# MCU.net
KiCad netlist of a schematic drawn in Altium Designer
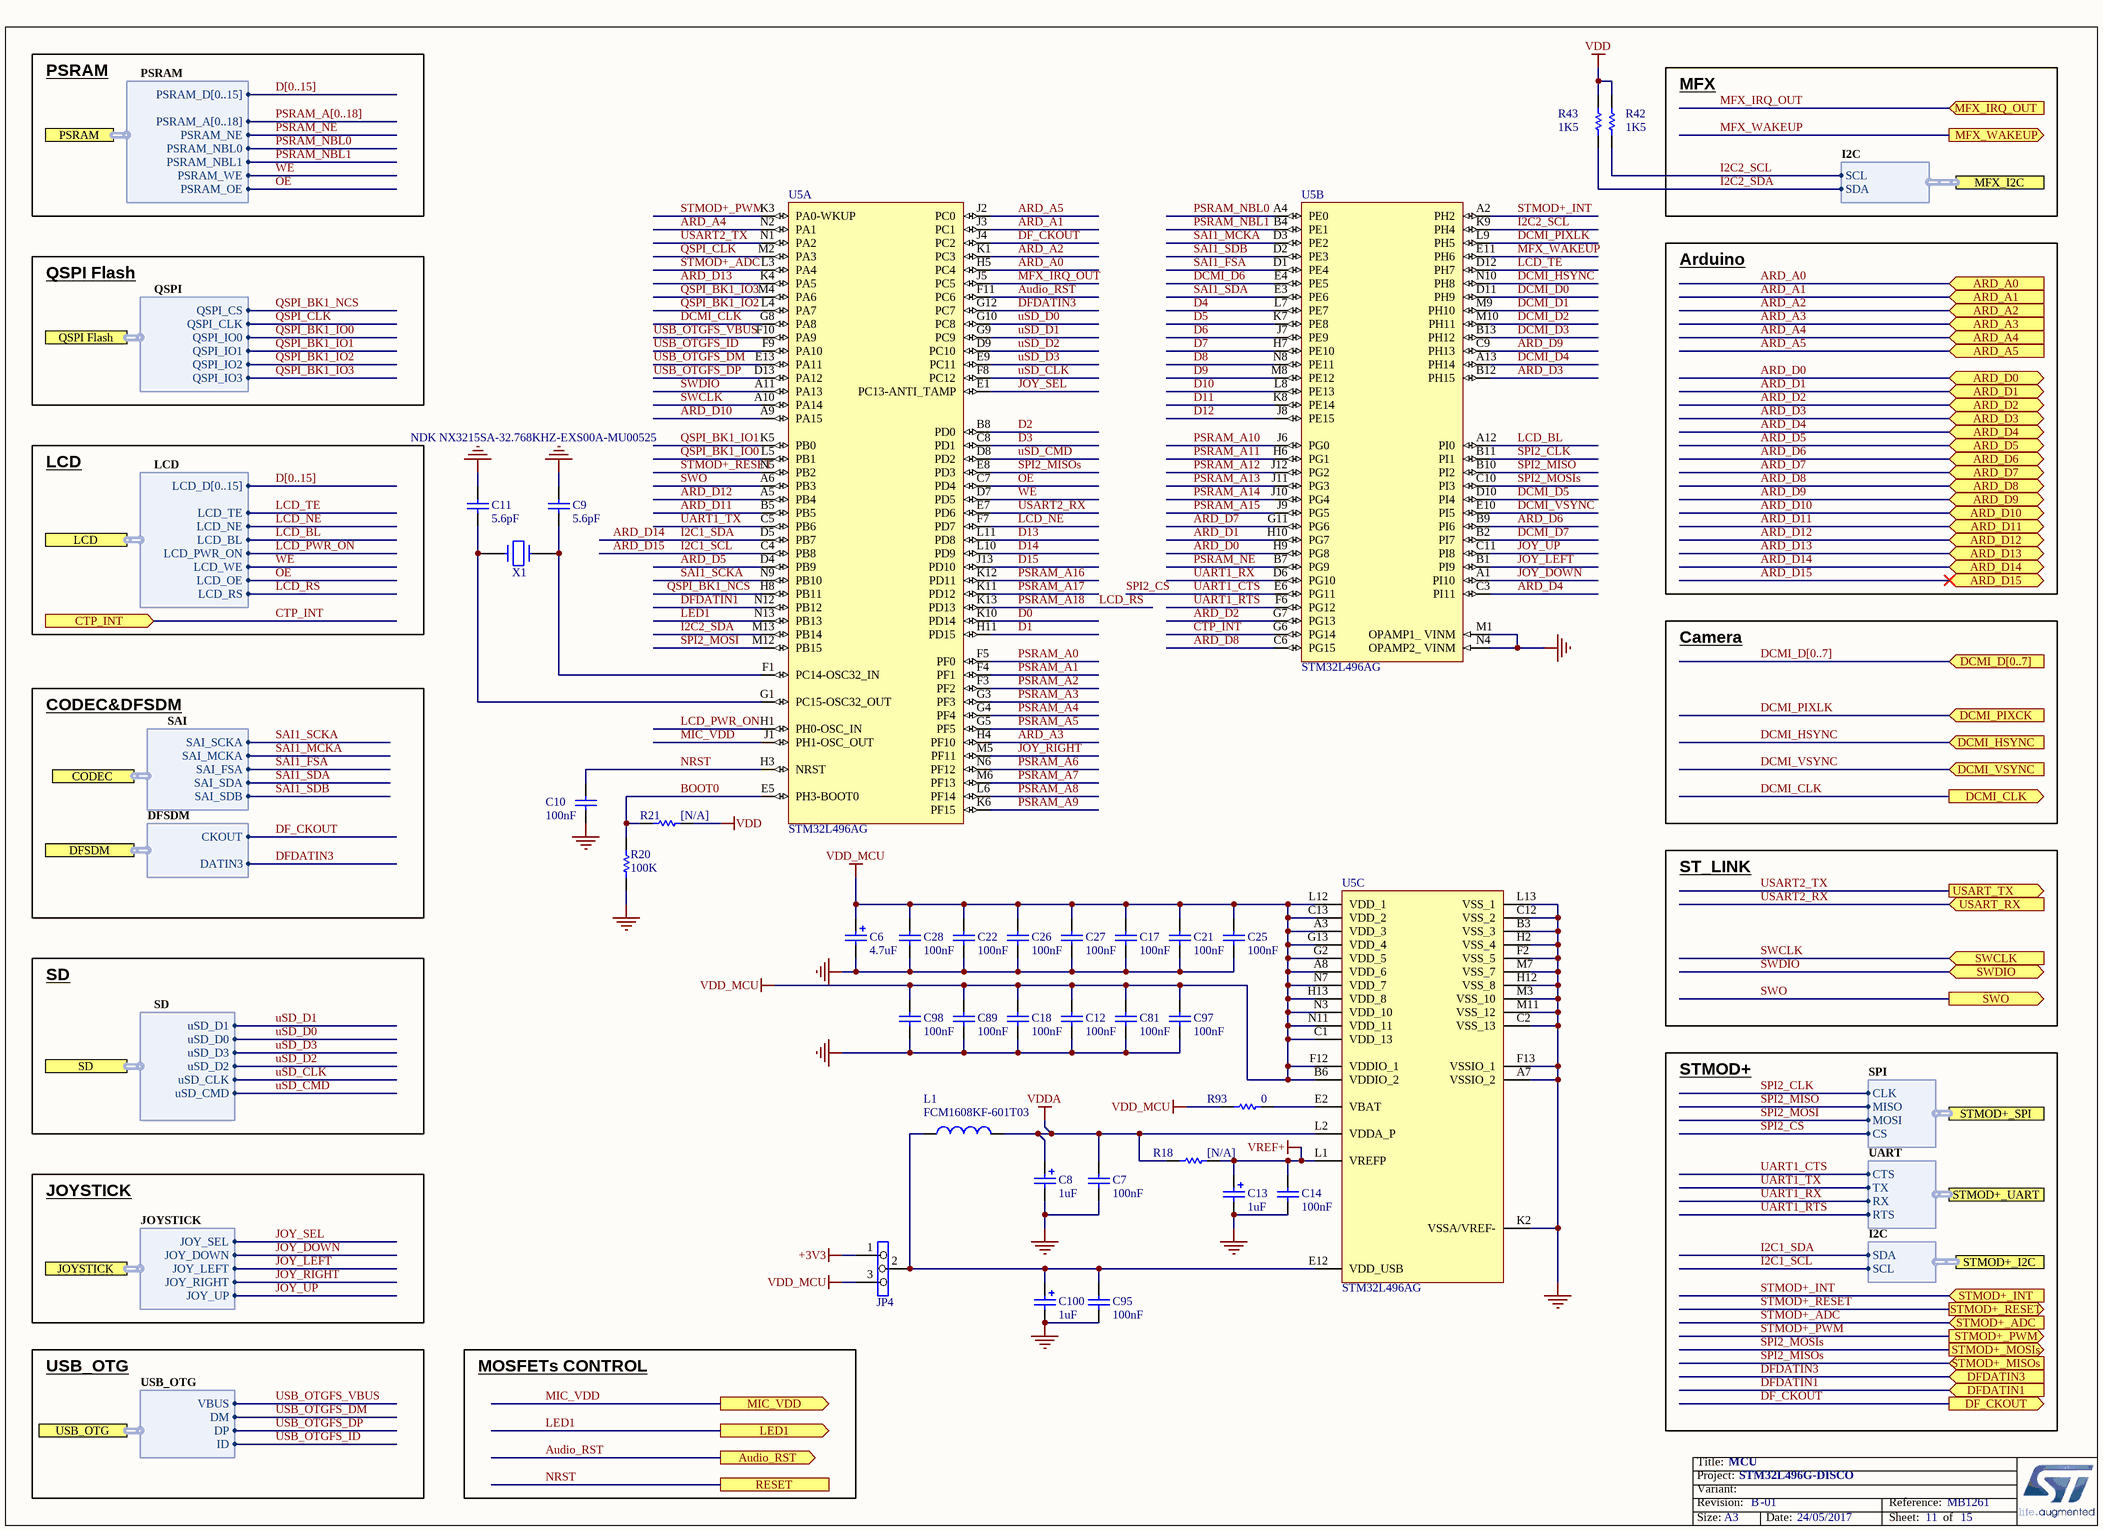
[diagram p0: MCU.SchDoc]

(export (version "E")
  (design (tool "Eeschema 10.0.6"))
  (components
    (comp (ref "C6")
      (value "4.7uF")
      (footprint "TAN-A")
      (description "TAN Capacitor,4.7uF,10%,16V,A Type,AVX")
      (fields (field (name "Comment") "TAJA475K016R") (field (name "PUBLISHER") "Altium Limited"))
      (libsource (lib "Miscellaneous Devices") (part "Cap Pol1"))
    )
    (comp (ref "C7")
      (value "100nF")
      (footprint "0603C")
      (description "Capacitor,100nF,10%,16V,X7R,0603,YAGEO")
      (fields (field (name "Comment") "CC0603KRX7R7BB104") (field (name "PUBLISHER") "Altium Limited"))
      (libsource (lib "Miscellaneous Devices") (part "Cap"))
    )
    (comp (ref "C8")
      (value "1uF")
      (footprint "TAN-A")
      (description "Tan Capacitor,1uF,10%,16V,Tan-A,TAJA105K016R")
      (fields (field (name "Comment") "TAJA105K016R") (field (name "PUBLISHER") "Altium Limited"))
      (libsource (lib "Miscellaneous Devices") (part "Cap Pol1"))
    )
    (comp (ref "C9")
      (value "5.6pF")
      (footprint "0603C")
      (description "Capacitor,5.6pF,0.25P,50V,NPO,0603")
      (fields (field (name "PUBLISHER") "Altium Limited"))
      (libsource (lib "Miscellaneous Devices") (part "Cap"))
    )
    (comp (ref "C10")
      (value "100nF")
      (footprint "0603C")
      (description "Capacitor,100nF,10%,16V,X7R,0603,YAGEO")
      (fields (field (name "Comment") "CC0603KRX7R7BB104") (field (name "PUBLISHER") "Altium Limited"))
      (libsource (lib "Miscellaneous Devices") (part "Cap"))
    )
    (comp (ref "C11")
      (value "5.6pF")
      (footprint "0603C")
      (description "Capacitor,5.6pF,0.25P,50V,NPO,0603")
      (fields (field (name "PUBLISHER") "Altium Limited"))
      (libsource (lib "Miscellaneous Devices") (part "Cap"))
    )
    (comp (ref "C12")
      (value "100nF")
      (footprint "0603C")
      (description "Capacitor,100nF,10%,16V,X7R,0603,YAGEO")
      (fields (field (name "Comment") "CC0603KRX7R7BB104") (field (name "PUBLISHER") "Altium Limited"))
      (libsource (lib "Miscellaneous Devices") (part "Cap"))
    )
    (comp (ref "C13")
      (value "1uF")
      (footprint "TAN-A")
      (description "Tan Capacitor,1uF,10%,16V,Tan-A,TAJA105K016R")
      (fields (field (name "Comment") "TAJA105K016R") (field (name "PUBLISHER") "Altium Limited"))
      (libsource (lib "Miscellaneous Devices") (part "Cap Pol1"))
    )
    (comp (ref "C14")
      (value "100nF")
      (footprint "0603C")
      (description "Capacitor,100nF,10%,16V,X7R,0603,YAGEO")
      (fields (field (name "Comment") "CC0603KRX7R7BB104") (field (name "PUBLISHER") "Altium Limited"))
      (libsource (lib "Miscellaneous Devices") (part "Cap"))
    )
    (comp (ref "C17")
      (value "100nF")
      (footprint "0603C")
      (description "Capacitor,100nF,10%,16V,X7R,0603,YAGEO")
      (fields (field (name "Comment") "CC0603KRX7R7BB104") (field (name "PUBLISHER") "Altium Limited"))
      (libsource (lib "Miscellaneous Devices") (part "Cap"))
    )
    (comp (ref "C18")
      (value "100nF")
      (footprint "0603C")
      (description "Capacitor,100nF,10%,16V,X7R,0603,YAGEO")
      (fields (field (name "Comment") "CC0603KRX7R7BB104") (field (name "PUBLISHER") "Altium Limited"))
      (libsource (lib "Miscellaneous Devices") (part "Cap"))
    )
    (comp (ref "C21")
      (value "100nF")
      (footprint "0603C")
      (description "Capacitor,100nF,10%,16V,X7R,0603,YAGEO")
      (fields (field (name "Comment") "CC0603KRX7R7BB104") (field (name "PUBLISHER") "Altium Limited"))
      (libsource (lib "Miscellaneous Devices") (part "Cap"))
    )
    (comp (ref "C22")
      (value "100nF")
      (footprint "0603C")
      (description "Capacitor,100nF,10%,16V,X7R,0603,YAGEO")
      (fields (field (name "Comment") "CC0603KRX7R7BB104") (field (name "PUBLISHER") "Altium Limited"))
      (libsource (lib "Miscellaneous Devices") (part "Cap"))
    )
    (comp (ref "C25")
      (value "100nF")
      (footprint "0603C")
      (description "Capacitor,100nF,10%,16V,X7R,0603,YAGEO")
      (fields (field (name "Comment") "CC0603KRX7R7BB104") (field (name "PUBLISHER") "Altium Limited"))
      (libsource (lib "Miscellaneous Devices") (part "Cap"))
    )
    (comp (ref "C26")
      (value "100nF")
      (footprint "0603C")
      (description "Capacitor,100nF,10%,16V,X7R,0603,YAGEO")
      (fields (field (name "Comment") "CC0603KRX7R7BB104") (field (name "PUBLISHER") "Altium Limited"))
      (libsource (lib "Miscellaneous Devices") (part "Cap"))
    )
    (comp (ref "C27")
      (value "100nF")
      (footprint "0603C")
      (description "Capacitor,100nF,10%,16V,X7R,0603,YAGEO")
      (fields (field (name "Comment") "CC0603KRX7R7BB104") (field (name "PUBLISHER") "Altium Limited"))
      (libsource (lib "Miscellaneous Devices") (part "Cap"))
    )
    (comp (ref "C28")
      (value "100nF")
      (footprint "0603C")
      (description "Capacitor,100nF,10%,16V,X7R,0603,YAGEO")
      (fields (field (name "Comment") "CC0603KRX7R7BB104") (field (name "PUBLISHER") "Altium Limited"))
      (libsource (lib "Miscellaneous Devices") (part "Cap"))
    )
    (comp (ref "C81")
      (value "100nF")
      (footprint "0603C")
      (description "Capacitor,100nF,10%,16V,X7R,0603,YAGEO")
      (fields (field (name "Comment") "CC0603KRX7R7BB104") (field (name "PUBLISHER") "Altium Limited"))
      (libsource (lib "Miscellaneous Devices") (part "Cap"))
    )
    (comp (ref "C89")
      (value "100nF")
      (footprint "0603C")
      (description "Capacitor,100nF,10%,16V,X7R,0603,YAGEO")
      (fields (field (name "Comment") "CC0603KRX7R7BB104") (field (name "PUBLISHER") "Altium Limited"))
      (libsource (lib "Miscellaneous Devices") (part "Cap"))
    )
    (comp (ref "C95")
      (value "100nF")
      (footprint "0603C")
      (description "Capacitor,100nF,10%,16V,X7R,0603,YAGEO")
      (fields (field (name "Comment") "CC0603KRX7R7BB104") (field (name "PUBLISHER") "Altium Limited"))
      (libsource (lib "Miscellaneous Devices") (part "Cap"))
    )
    (comp (ref "C97")
      (value "100nF")
      (footprint "0603C")
      (description "Capacitor,100nF,10%,16V,X7R,0603,YAGEO")
      (fields (field (name "Comment") "CC0603KRX7R7BB104") (field (name "PUBLISHER") "Altium Limited"))
      (libsource (lib "Miscellaneous Devices") (part "Cap"))
    )
    (comp (ref "C98")
      (value "100nF")
      (footprint "0603C")
      (description "Capacitor,100nF,10%,16V,X7R,0603,YAGEO")
      (fields (field (name "Comment") "CC0603KRX7R7BB104") (field (name "PUBLISHER") "Altium Limited"))
      (libsource (lib "Miscellaneous Devices") (part "Cap"))
    )
    (comp (ref "C100")
      (value "1uF")
      (footprint "TAN-A")
      (description "Tan Capacitor,1uF,10%,16V,Tan-A,TAJA105K016R")
      (fields (field (name "Comment") "TAJA105K016R") (field (name "PUBLISHER") "Altium Limited"))
      (libsource (lib "Miscellaneous Devices") (part "Cap Pol1"))
    )
    (comp (ref "JP4") (value "Jumper3") (footprint "SIP3") (libsource (lib "STR910_SCHLIB") (part "Jumper3")))
    (comp (ref "L1")
      (value "FCM1608KF-601T03")
      (footprint "0603L")
      (description "100uH Bead")
      (fields (field (name "PUBLISHER") "Altium Limited"))
      (libsource (lib "Miscellaneous Devices") (part "Inductor"))
    )
    (comp (ref "R18")
      (value "[N/A]")
      (footprint "0603R")
      (description "Resistor, 0 ,0603,1%,YAGEO")
      (fields (field (name "PUBLISHER") "Altium Limited"))
      (libsource (lib "Miscellaneous Devices") (part "res1"))
    )
    (comp (ref "R20")
      (value "100K")
      (footprint "0603R")
      (description "Resistor,100K,0603,1%,YAGEO")
      (fields (field (name "Comment") "RC0603FR-07100KL") (field (name "PUBLISHER") "Altium Limited"))
      (libsource (lib "Miscellaneous Devices") (part "res1"))
    )
    (comp (ref "R21")
      (value "[N/A]")
      (footprint "0603R")
      (description "Resistor,100K,0603,1%,YAGEO")
      (fields (field (name "PUBLISHER") "Altium Limited"))
      (libsource (lib "Miscellaneous Devices") (part "res1"))
    )
    (comp (ref "R42")
      (value "1K5")
      (footprint "0603R")
      (description "Resistor,1.5K,0603,1%,YAGEO")
      (fields (field (name "Comment") "RC0603FR-071K5L") (field (name "PUBLISHER") "Altium Limited"))
      (libsource (lib "Miscellaneous Devices") (part "res1"))
    )
    (comp (ref "R43")
      (value "1K5")
      (footprint "0603R")
      (description "Resistor,1.5K,0603,1%,YAGEO")
      (fields (field (name "Comment") "RC0603FR-071K5L") (field (name "PUBLISHER") "Altium Limited"))
      (libsource (lib "Miscellaneous Devices") (part "res1"))
    )
    (comp (ref "R93")
      (value "0")
      (footprint "0603R")
      (description "Resistor, 0 ,0603,1%,YAGEO")
      (fields (field (name "Comment") "RC0603JR-070RL") (field (name "PUBLISHER") "Altium Limited"))
      (libsource (lib "Miscellaneous Devices") (part "res1"))
    )
    (comp (ref "U5")
      (value "STM32L496AG")
      (footprint "FBGA169_0R5_7X7")
      (libsource (lib "Big Orca") (part "STM32L496G"))
    )
    (comp (ref "X1")
      (value "NDK NX3215SA-32.768KHZ-EXS00A-MU00525")
      (footprint "XTAL_2SM_3R2X1R5")
      (description "32.768kHz Crystal")
      (libsource (lib "MB1167") (part "CRYSTAL_32K"))
    )
  )
  (nets
    (net (code "12") (name "+3V3") (class "Default") (node (ref "JP4") (pin "1") (pintype "passive")))
    (net (code "13") (name "/ARD_A0") (class "Default")
      (node (ref "U5") (pin "H5") (pinfunction "PC4_H5") (pintype "bidirectional"))
    )
    (net (code "14") (name "/ARD_A1") (class "Default")
      (node (ref "U5") (pin "J3") (pinfunction "PC1_J3") (pintype "bidirectional"))
    )
    (net (code "15") (name "/ARD_A2") (class "Default")
      (node (ref "U5") (pin "K1") (pinfunction "PC3_K1") (pintype "bidirectional"))
    )
    (net (code "16") (name "/ARD_A3") (class "Default")
      (node (ref "U5") (pin "H4") (pinfunction "PF10_H4") (pintype "bidirectional"))
    )
    (net (code "17") (name "/ARD_A4") (class "Default")
      (node (ref "U5") (pin "N2") (pinfunction "PA1_N2") (pintype "bidirectional"))
    )
    (net (code "18") (name "/ARD_A5") (class "Default")
      (node (ref "U5") (pin "J2") (pinfunction "PC0_J2") (pintype "bidirectional"))
    )
    (net (code "19") (name "/ARD_D0") (class "Default")
      (node (ref "U5") (pin "H9") (pinfunction "PG8_H9") (pintype "bidirectional"))
    )
    (net (code "20") (name "/ARD_D1") (class "Default")
      (node (ref "U5") (pin "H10") (pinfunction "PG7_H10") (pintype "bidirectional"))
    )
    (net (code "21") (name "/ARD_D2") (class "Default")
      (node (ref "U5") (pin "G7") (pinfunction "PG13_G7") (pintype "bidirectional"))
    )
    (net (code "22") (name "/ARD_D3") (class "Default")
      (node (ref "U5") (pin "B12") (pinfunction "PH15_B12") (pintype "bidirectional"))
    )
    (net (code "23") (name "/ARD_D4") (class "Default")
      (node (ref "U5") (pin "C3") (pinfunction "PI11_C3") (pintype "bidirectional"))
    )
    (net (code "24") (name "/ARD_D5") (class "Default")
      (node (ref "U5") (pin "D4") (pinfunction "PB9_D4") (pintype "bidirectional"))
    )
    (net (code "25") (name "/ARD_D6") (class "Default")
      (node (ref "U5") (pin "B9") (pinfunction "PI6_B9") (pintype "bidirectional"))
    )
    (net (code "26") (name "/ARD_D7") (class "Default")
      (node (ref "U5") (pin "G11") (pinfunction "PG6_G11") (pintype "bidirectional"))
    )
    (net (code "27") (name "/ARD_D8") (class "Default")
      (node (ref "U5") (pin "C6") (pinfunction "PG15_C6") (pintype "bidirectional"))
    )
    (net (code "28") (name "/ARD_D9") (class "Default")
      (node (ref "U5") (pin "C9") (pinfunction "PH13_C9") (pintype "bidirectional"))
    )
    (net (code "29") (name "/ARD_D10") (class "Default")
      (node (ref "U5") (pin "A9") (pinfunction "PA15_A9") (pintype "bidirectional"))
    )
    (net (code "30") (name "/ARD_D11") (class "Default")
      (node (ref "U5") (pin "B5") (pinfunction "PB5_B5") (pintype "bidirectional"))
    )
    (net (code "31") (name "/ARD_D12") (class "Default")
      (node (ref "U5") (pin "A5") (pinfunction "PB4_A5") (pintype "bidirectional"))
    )
    (net (code "32") (name "/ARD_D13") (class "Default")
      (node (ref "U5") (pin "K4") (pinfunction "PA5_K4") (pintype "bidirectional"))
    )
    (net (code "33") (name "/ARD_D14") (class "Default")
      (node (ref "U5") (pin "D5") (pinfunction "PB7_D5") (pintype "bidirectional"))
    )
    (net (code "34") (name "/ARD_D15") (class "Default")
      (node (ref "U5") (pin "C4") (pinfunction "PB8_C4") (pintype "bidirectional+no_connect"))
    )
    (net (code "35") (name "/Audio_RST") (class "Default")
      (node (ref "U5") (pin "F11") (pinfunction "PC6_F11") (pintype "bidirectional"))
    )
    (net (code "36") (name "/BOOT0") (class "Default")
      (node (ref "R20") (pin "2") (pinfunction "2_2") (pintype "passive"))
      (node (ref "R21") (pin "2") (pinfunction "2_2") (pintype "passive"))
      (node (ref "U5") (pin "E5") (pinfunction "PH3-BOOT0_E5") (pintype "bidirectional"))
    )
    (net (code "37") (name "/CTP_INT") (class "Default")
      (node (ref "U5") (pin "G6") (pinfunction "PG14_G6") (pintype "bidirectional"))
    )
    (net (code "38") (name "/D0") (class "Default")
      (node (ref "U5") (pin "K10") (pinfunction "PD14_K10") (pintype "bidirectional"))
    )
    (net (code "39") (name "/D1") (class "Default")
      (node (ref "U5") (pin "H11") (pinfunction "PD15_H11") (pintype "bidirectional"))
    )
    (net (code "40") (name "/D2") (class "Default")
      (node (ref "U5") (pin "B8") (pinfunction "PD0_B8") (pintype "bidirectional"))
    )
    (net (code "41") (name "/D3") (class "Default")
      (node (ref "U5") (pin "C8") (pinfunction "PD1_C8") (pintype "bidirectional"))
    )
    (net (code "42") (name "/D4") (class "Default")
      (node (ref "U5") (pin "L7") (pinfunction "PE7_L7") (pintype "bidirectional"))
    )
    (net (code "43") (name "/D5") (class "Default")
      (node (ref "U5") (pin "K7") (pinfunction "PE8_K7") (pintype "bidirectional"))
    )
    (net (code "44") (name "/D6") (class "Default")
      (node (ref "U5") (pin "J7") (pinfunction "PE9_J7") (pintype "bidirectional"))
    )
    (net (code "45") (name "/D7") (class "Default")
      (node (ref "U5") (pin "H7") (pinfunction "PE10_H7") (pintype "bidirectional"))
    )
    (net (code "46") (name "/D8") (class "Default")
      (node (ref "U5") (pin "N8") (pinfunction "PE11_N8") (pintype "bidirectional"))
    )
    (net (code "47") (name "/D9") (class "Default")
      (node (ref "U5") (pin "M8") (pinfunction "PE12_M8") (pintype "bidirectional"))
    )
    (net (code "48") (name "/D10") (class "Default")
      (node (ref "U5") (pin "L8") (pinfunction "PE13_L8") (pintype "bidirectional"))
    )
    (net (code "49") (name "/D11") (class "Default")
      (node (ref "U5") (pin "K8") (pinfunction "PE14_K8") (pintype "bidirectional"))
    )
    (net (code "50") (name "/D12") (class "Default")
      (node (ref "U5") (pin "J8") (pinfunction "PE15_J8") (pintype "bidirectional"))
    )
    (net (code "51") (name "/D13") (class "Default")
      (node (ref "U5") (pin "L11") (pinfunction "PD8_L11") (pintype "bidirectional"))
    )
    (net (code "52") (name "/D14") (class "Default")
      (node (ref "U5") (pin "L10") (pinfunction "PD9_L10") (pintype "bidirectional"))
    )
    (net (code "53") (name "/D15") (class "Default")
      (node (ref "U5") (pin "J13") (pinfunction "PD10_J13") (pintype "bidirectional"))
    )
    (net (code "54") (name "/DCMI_CLK") (class "Default")
      (node (ref "U5") (pin "G8") (pinfunction "PA8_G8") (pintype "bidirectional"))
    )
    (net (code "55") (name "/DCMI_D0") (class "Default")
      (node (ref "U5") (pin "D11") (pinfunction "PH9_D11") (pintype "bidirectional"))
    )
    (net (code "56") (name "/DCMI_D1") (class "Default")
      (node (ref "U5") (pin "M9") (pinfunction "PH10_M9") (pintype "bidirectional"))
    )
    (net (code "57") (name "/DCMI_D2") (class "Default")
      (node (ref "U5") (pin "M10") (pinfunction "PH11_M10") (pintype "bidirectional"))
    )
    (net (code "58") (name "/DCMI_D3") (class "Default")
      (node (ref "U5") (pin "B13") (pinfunction "PH12_B13") (pintype "bidirectional"))
    )
    (net (code "59") (name "/DCMI_D4") (class "Default")
      (node (ref "U5") (pin "A13") (pinfunction "PH14_A13") (pintype "bidirectional"))
    )
    (net (code "60") (name "/DCMI_D5") (class "Default")
      (node (ref "U5") (pin "D10") (pinfunction "PI4_D10") (pintype "bidirectional"))
    )
    (net (code "61") (name "/DCMI_D6") (class "Default")
      (node (ref "U5") (pin "E4") (pinfunction "PE5_E4") (pintype "bidirectional"))
    )
    (net (code "62") (name "/DCMI_D7") (class "Default")
      (node (ref "U5") (pin "B2") (pinfunction "PI7_B2") (pintype "bidirectional"))
    )
    (net (code "64") (name "/DCMI_HSYNC") (class "Default")
      (node (ref "U5") (pin "N10") (pinfunction "PH8_N10") (pintype "bidirectional"))
    )
    (net (code "65") (name "/DCMI_PIXLK") (class "Default")
      (node (ref "U5") (pin "L9") (pinfunction "PH5_L9") (pintype "bidirectional"))
    )
    (net (code "66") (name "/DCMI_VSYNC") (class "Default")
      (node (ref "U5") (pin "E10") (pinfunction "PI5_E10") (pintype "bidirectional"))
    )
    (net (code "67") (name "/DFDATIN1") (class "Default")
      (node (ref "U5") (pin "N12") (pinfunction "PB12_N12") (pintype "bidirectional"))
    )
    (net (code "68") (name "/DFDATIN3") (class "Default")
      (node (ref "U5") (pin "G12") (pinfunction "PC7_G12") (pintype "bidirectional"))
    )
    (net (code "69") (name "/DF_CKOUT") (class "Default")
      (node (ref "U5") (pin "J4") (pinfunction "PC2_J4") (pintype "bidirectional"))
    )
    (net (code "71") (name "/I2C2_SCL") (class "Default")
      (node (ref "R42") (pin "2") (pinfunction "2_2") (pintype "passive"))
      (node (ref "U5") (pin "K9") (pinfunction "PH4_K9") (pintype "bidirectional"))
    )
    (net (code "72") (name "/I2C2_SDA") (class "Default")
      (node (ref "R43") (pin "2") (pinfunction "2_2") (pintype "passive"))
      (node (ref "U5") (pin "M13") (pinfunction "PB14_M13") (pintype "bidirectional"))
    )
    (net (code "73") (name "/JOY_DOWN") (class "Default")
      (node (ref "U5") (pin "A1") (pinfunction "PI10_A1") (pintype "bidirectional"))
    )
    (net (code "74") (name "/JOY_LEFT") (class "Default")
      (node (ref "U5") (pin "B1") (pinfunction "PI9_B1") (pintype "bidirectional"))
    )
    (net (code "75") (name "/JOY_RIGHT") (class "Default")
      (node (ref "U5") (pin "M5") (pinfunction "PF11_M5") (pintype "bidirectional"))
    )
    (net (code "76") (name "/JOY_SEL") (class "Default")
      (node (ref "U5") (pin "E1") (pinfunction "PC13-ANTI_TAMP_E1") (pintype "bidirectional"))
    )
    (net (code "77") (name "/JOY_UP") (class "Default")
      (node (ref "U5") (pin "C11") (pinfunction "PI8_C11") (pintype "bidirectional"))
    )
    (net (code "78") (name "/LCD_BL") (class "Default")
      (node (ref "U5") (pin "A12") (pinfunction "PI0_A12") (pintype "bidirectional"))
    )
    (net (code "79") (name "/LCD_NE") (class "Default")
      (node (ref "U5") (pin "F7") (pinfunction "PD7_F7") (pintype "bidirectional"))
    )
    (net (code "80") (name "/LCD_PWR_ON") (class "Default")
      (node (ref "U5") (pin "H1") (pinfunction "PH0-OSC_IN_H1") (pintype "bidirectional"))
    )
    (net (code "81") (name "/LCD_RS") (class "Default")
      (node (ref "U5") (pin "K13") (pinfunction "PD13_K13") (pintype "bidirectional"))
    )
    (net (code "82") (name "/LCD_TE") (class "Default")
      (node (ref "U5") (pin "D12") (pinfunction "PH7_D12") (pintype "bidirectional"))
    )
    (net (code "84") (name "/LED1") (class "Default")
      (node (ref "U5") (pin "N13") (pinfunction "PB13_N13") (pintype "bidirectional"))
    )
    (net (code "85") (name "/MFX_IRQ_OUT") (class "Default")
      (node (ref "U5") (pin "J5") (pinfunction "PC5_J5") (pintype "bidirectional"))
    )
    (net (code "86") (name "/MFX_WAKEUP") (class "Default")
      (node (ref "U5") (pin "E11") (pinfunction "PH6_E11") (pintype "bidirectional"))
    )
    (net (code "87") (name "/MIC_VDD") (class "Default")
      (node (ref "U5") (pin "J1") (pinfunction "PH1-OSC_OUT_J1") (pintype "bidirectional"))
    )
    (net (code "88") (name "/NRST") (class "Default")
      (node (ref "C10") (pin "1") (pinfunction "1_1") (pintype "passive"))
      (node (ref "U5") (pin "H3") (pinfunction "NRST_H3") (pintype "bidirectional"))
    )
    (net (code "89") (name "/OE") (class "Default")
      (node (ref "U5") (pin "C7") (pinfunction "PD4_C7") (pintype "bidirectional"))
    )
    (net (code "90") (name "/PSRAM_A0") (class "Default")
      (node (ref "U5") (pin "F5") (pinfunction "PF0_F5") (pintype "bidirectional"))
    )
    (net (code "91") (name "/PSRAM_A1") (class "Default")
      (node (ref "U5") (pin "F4") (pinfunction "PF1_F4") (pintype "bidirectional"))
    )
    (net (code "92") (name "/PSRAM_A2") (class "Default")
      (node (ref "U5") (pin "F3") (pinfunction "PF2_F3") (pintype "bidirectional"))
    )
    (net (code "93") (name "/PSRAM_A3") (class "Default")
      (node (ref "U5") (pin "G3") (pinfunction "PF3_G3") (pintype "bidirectional"))
    )
    (net (code "94") (name "/PSRAM_A4") (class "Default")
      (node (ref "U5") (pin "G4") (pinfunction "PF4_G4") (pintype "bidirectional"))
    )
    (net (code "95") (name "/PSRAM_A5") (class "Default")
      (node (ref "U5") (pin "G5") (pinfunction "PF5_G5") (pintype "bidirectional"))
    )
    (net (code "96") (name "/PSRAM_A6") (class "Default")
      (node (ref "U5") (pin "N6") (pinfunction "PF12_N6") (pintype "bidirectional"))
    )
    (net (code "97") (name "/PSRAM_A7") (class "Default")
      (node (ref "U5") (pin "M6") (pinfunction "PF13_M6") (pintype "bidirectional"))
    )
    (net (code "98") (name "/PSRAM_A8") (class "Default")
      (node (ref "U5") (pin "L6") (pinfunction "PF14_L6") (pintype "bidirectional"))
    )
    (net (code "99") (name "/PSRAM_A9") (class "Default")
      (node (ref "U5") (pin "K6") (pinfunction "PF15_K6") (pintype "bidirectional"))
    )
    (net (code "100") (name "/PSRAM_A10") (class "Default")
      (node (ref "U5") (pin "J6") (pinfunction "PG0_J6") (pintype "bidirectional"))
    )
    (net (code "101") (name "/PSRAM_A11") (class "Default")
      (node (ref "U5") (pin "H6") (pinfunction "PG1_H6") (pintype "bidirectional"))
    )
    (net (code "102") (name "/PSRAM_A12") (class "Default")
      (node (ref "U5") (pin "J12") (pinfunction "PG2_J12") (pintype "bidirectional"))
    )
    (net (code "103") (name "/PSRAM_A13") (class "Default")
      (node (ref "U5") (pin "J11") (pinfunction "PG3_J11") (pintype "bidirectional"))
    )
    (net (code "104") (name "/PSRAM_A14") (class "Default")
      (node (ref "U5") (pin "J10") (pinfunction "PG4_J10") (pintype "bidirectional"))
    )
    (net (code "105") (name "/PSRAM_A15") (class "Default")
      (node (ref "U5") (pin "J9") (pinfunction "PG5_J9") (pintype "bidirectional"))
    )
    (net (code "106") (name "/PSRAM_A16") (class "Default")
      (node (ref "U5") (pin "K12") (pinfunction "PD11_K12") (pintype "bidirectional"))
    )
    (net (code "107") (name "/PSRAM_A17") (class "Default")
      (node (ref "U5") (pin "K11") (pinfunction "PD12_K11") (pintype "bidirectional"))
    )
    (net (code "108") (name "/PSRAM_NBL0") (class "Default")
      (node (ref "U5") (pin "A4") (pinfunction "PE0_A4") (pintype "bidirectional"))
    )
    (net (code "109") (name "/PSRAM_NBL1") (class "Default")
      (node (ref "U5") (pin "B4") (pinfunction "PE1_B4") (pintype "bidirectional"))
    )
    (net (code "110") (name "/PSRAM_NE") (class "Default")
      (node (ref "U5") (pin "B7") (pinfunction "PG9_B7") (pintype "bidirectional"))
    )
    (net (code "112") (name "/QSPI_BK1_IO0") (class "Default")
      (node (ref "U5") (pin "L5") (pinfunction "PB1_L5") (pintype "bidirectional"))
    )
    (net (code "113") (name "/QSPI_BK1_IO1") (class "Default")
      (node (ref "U5") (pin "K5") (pinfunction "PB0_K5") (pintype "bidirectional"))
    )
    (net (code "114") (name "/QSPI_BK1_IO2") (class "Default")
      (node (ref "U5") (pin "L4") (pinfunction "PA7_L4") (pintype "bidirectional"))
    )
    (net (code "115") (name "/QSPI_BK1_IO3") (class "Default")
      (node (ref "U5") (pin "M4") (pinfunction "PA6_M4") (pintype "bidirectional"))
    )
    (net (code "116") (name "/QSPI_BK1_NCS") (class "Default")
      (node (ref "U5") (pin "H8") (pinfunction "PB11_H8") (pintype "bidirectional"))
    )
    (net (code "117") (name "/QSPI_CLK") (class "Default")
      (node (ref "U5") (pin "M2") (pinfunction "PA3_M2") (pintype "bidirectional"))
    )
    (net (code "118") (name "/SAI1_FSA") (class "Default")
      (node (ref "U5") (pin "D1") (pinfunction "PE4_D1") (pintype "bidirectional"))
    )
    (net (code "119") (name "/SAI1_MCKA") (class "Default")
      (node (ref "U5") (pin "D3") (pinfunction "PE2_D3") (pintype "bidirectional"))
    )
    (net (code "120") (name "/SAI1_SCKA") (class "Default")
      (node (ref "U5") (pin "N9") (pinfunction "PB10_N9") (pintype "bidirectional"))
    )
    (net (code "121") (name "/SAI1_SDA") (class "Default")
      (node (ref "U5") (pin "E3") (pinfunction "PE6_E3") (pintype "bidirectional"))
    )
    (net (code "122") (name "/SAI1_SDB") (class "Default")
      (node (ref "U5") (pin "D2") (pinfunction "PE3_D2") (pintype "bidirectional"))
    )
    (net (code "123") (name "/SPI2_CLK") (class "Default")
      (node (ref "U5") (pin "B11") (pinfunction "PI1_B11") (pintype "bidirectional"))
    )
    (net (code "124") (name "/SPI2_CS") (class "Default")
      (node (ref "U5") (pin "E6") (pinfunction "PG11_E6") (pintype "bidirectional"))
    )
    (net (code "125") (name "/SPI2_MISO") (class "Default")
      (node (ref "U5") (pin "B10") (pinfunction "PI2_B10") (pintype "bidirectional"))
    )
    (net (code "126") (name "/SPI2_MISOs") (class "Default")
      (node (ref "U5") (pin "E8") (pinfunction "PD3_E8") (pintype "bidirectional"))
    )
    (net (code "127") (name "/SPI2_MOSI") (class "Default")
      (node (ref "U5") (pin "M12") (pinfunction "PB15_M12") (pintype "bidirectional"))
    )
    (net (code "128") (name "/SPI2_MOSIs") (class "Default")
      (node (ref "U5") (pin "C10") (pinfunction "PI3_C10") (pintype "bidirectional"))
    )
    (net (code "129") (name "/STMOD+_ADC") (class "Default")
      (node (ref "U5") (pin "L3") (pinfunction "PA4_L3") (pintype "bidirectional"))
    )
    (net (code "130") (name "/STMOD+_INT") (class "Default")
      (node (ref "U5") (pin "A2") (pinfunction "PH2_A2") (pintype "bidirectional"))
    )
    (net (code "131") (name "/STMOD+_PWM") (class "Default")
      (node (ref "U5") (pin "K3") (pinfunction "PA0-WKUP_K3") (pintype "bidirectional"))
    )
    (net (code "132") (name "/STMOD+_RESET") (class "Default")
      (node (ref "U5") (pin "N5") (pinfunction "PB2_N5") (pintype "bidirectional"))
    )
    (net (code "133") (name "/SWCLK") (class "Default")
      (node (ref "U5") (pin "A10") (pinfunction "PA14_A10") (pintype "bidirectional"))
    )
    (net (code "134") (name "/SWDIO") (class "Default")
      (node (ref "U5") (pin "A11") (pinfunction "PA13_A11") (pintype "bidirectional"))
    )
    (net (code "135") (name "/SWO") (class "Default")
      (node (ref "U5") (pin "A6") (pinfunction "PB3_A6") (pintype "bidirectional"))
    )
    (net (code "136") (name "/UART1_RTS") (class "Default")
      (node (ref "U5") (pin "F6") (pinfunction "PG12_F6") (pintype "bidirectional"))
    )
    (net (code "137") (name "/UART1_RX") (class "Default")
      (node (ref "U5") (pin "D6") (pinfunction "PG10_D6") (pintype "bidirectional"))
    )
    (net (code "138") (name "/UART1_TX") (class "Default")
      (node (ref "U5") (pin "C5") (pinfunction "PB6_C5") (pintype "bidirectional"))
    )
    (net (code "139") (name "/USART2_RX") (class "Default")
      (node (ref "U5") (pin "E7") (pinfunction "PD6_E7") (pintype "bidirectional"))
    )
    (net (code "140") (name "/USART2_TX") (class "Default")
      (node (ref "U5") (pin "N1") (pinfunction "PA2_N1") (pintype "bidirectional"))
    )
    (net (code "141") (name "/USB_OTGFS_DM") (class "Default")
      (node (ref "U5") (pin "E13") (pinfunction "PA11_E13") (pintype "bidirectional"))
    )
    (net (code "142") (name "/USB_OTGFS_DP") (class "Default")
      (node (ref "U5") (pin "D13") (pinfunction "PA12_D13") (pintype "bidirectional"))
    )
    (net (code "143") (name "/USB_OTGFS_ID") (class "Default")
      (node (ref "U5") (pin "F9") (pinfunction "PA10_F9") (pintype "bidirectional"))
    )
    (net (code "144") (name "/USB_OTGFS_VBUS") (class "Default")
      (node (ref "U5") (pin "F10") (pinfunction "PA9_F10") (pintype "bidirectional"))
    )
    (net (code "145") (name "/WE") (class "Default")
      (node (ref "U5") (pin "D7") (pinfunction "PD5_D7") (pintype "bidirectional"))
    )
    (net (code "146") (name "/uSD_CLK") (class "Default")
      (node (ref "U5") (pin "F8") (pinfunction "PC12_F8") (pintype "bidirectional"))
    )
    (net (code "147") (name "/uSD_CMD") (class "Default")
      (node (ref "U5") (pin "D8") (pinfunction "PD2_D8") (pintype "bidirectional"))
    )
    (net (code "148") (name "/uSD_D0") (class "Default")
      (node (ref "U5") (pin "G10") (pinfunction "PC8_G10") (pintype "bidirectional"))
    )
    (net (code "149") (name "/uSD_D1") (class "Default")
      (node (ref "U5") (pin "G9") (pinfunction "PC9_G9") (pintype "bidirectional"))
    )
    (net (code "150") (name "/uSD_D2") (class "Default")
      (node (ref "U5") (pin "D9") (pinfunction "PC10_D9") (pintype "bidirectional"))
    )
    (net (code "151") (name "/uSD_D3") (class "Default")
      (node (ref "U5") (pin "E9") (pinfunction "PC11_E9") (pintype "bidirectional"))
    )
    (net (code "163") (name "GND") (class "Default")
      (node (ref "C10") (pin "2") (pinfunction "2_2") (pintype "passive"))
      (node (ref "C100") (pin "2") (pinfunction "2_2") (pintype "passive"))
      (node (ref "C11") (pin "1") (pinfunction "1_1") (pintype "passive"))
      (node (ref "C12") (pin "2") (pinfunction "2_2") (pintype "passive"))
      (node (ref "C13") (pin "2") (pinfunction "2_2") (pintype "passive"))
      (node (ref "C14") (pin "2") (pinfunction "2_2") (pintype "passive"))
      (node (ref "C17") (pin "2") (pinfunction "2_2") (pintype "passive"))
      (node (ref "C18") (pin "2") (pinfunction "2_2") (pintype "passive"))
      (node (ref "C21") (pin "2") (pinfunction "2_2") (pintype "passive"))
      (node (ref "C22") (pin "2") (pinfunction "2_2") (pintype "passive"))
      (node (ref "C25") (pin "2") (pinfunction "2_2") (pintype "passive"))
      (node (ref "C26") (pin "2") (pinfunction "2_2") (pintype "passive"))
      (node (ref "C27") (pin "2") (pinfunction "2_2") (pintype "passive"))
      (node (ref "C28") (pin "2") (pinfunction "2_2") (pintype "passive"))
      (node (ref "C6") (pin "2") (pinfunction "2_2") (pintype "passive"))
      (node (ref "C7") (pin "2") (pinfunction "2_2") (pintype "passive"))
      (node (ref "C8") (pin "2") (pinfunction "2_2") (pintype "passive"))
      (node (ref "C81") (pin "2") (pinfunction "2_2") (pintype "passive"))
      (node (ref "C89") (pin "2") (pinfunction "2_2") (pintype "passive"))
      (node (ref "C9") (pin "1") (pinfunction "1_1") (pintype "passive"))
      (node (ref "C95") (pin "2") (pinfunction "2_2") (pintype "passive"))
      (node (ref "C97") (pin "2") (pinfunction "2_2") (pintype "passive"))
      (node (ref "C98") (pin "2") (pinfunction "2_2") (pintype "passive"))
      (node (ref "R20") (pin "1") (pinfunction "1_1") (pintype "passive"))
      (node (ref "U5") (pin "A7") (pinfunction "VSSIO_2_A7") (pintype "power_in"))
      (node (ref "U5") (pin "B3") (pinfunction "VSS_3_B3") (pintype "power_in"))
      (node (ref "U5") (pin "C12") (pinfunction "VSS_2_C12") (pintype "power_in"))
      (node (ref "U5") (pin "C2") (pinfunction "VSS_13_C2") (pintype "power_in"))
      (node (ref "U5") (pin "F13") (pinfunction "VSSIO_1_F13") (pintype "power_in"))
      (node (ref "U5") (pin "F2") (pinfunction "VSS_5_F2") (pintype "power_in"))
      (node (ref "U5") (pin "H12") (pinfunction "VSS_8_H12") (pintype "power_in"))
      (node (ref "U5") (pin "H2") (pinfunction "VSS_4_H2") (pintype "power_in"))
      (node (ref "U5") (pin "K2") (pinfunction "VSSA/VREF-_K2") (pintype "power_in"))
      (node (ref "U5") (pin "L13") (pinfunction "VSS_1_L13") (pintype "power_in"))
      (node (ref "U5") (pin "M1") (pinfunction "OPAMP1__VINM_M1") (pintype "input"))
      (node (ref "U5") (pin "M11") (pinfunction "VSS_12_M11") (pintype "power_in"))
      (node (ref "U5") (pin "M3") (pinfunction "VSS_10_M3") (pintype "power_in"))
      (node (ref "U5") (pin "M7") (pinfunction "VSS_7_M7") (pintype "power_in"))
      (node (ref "U5") (pin "N4") (pinfunction "OPAMP2__VINM_N4") (pintype "input"))
    )
    (net (code "164") (name "Net-(U5A-PC14-OSC32_IN)") (class "Default")
      (node (ref "C9") (pin "2") (pinfunction "2_2") (pintype "passive"))
      (node (ref "U5") (pin "F1") (pinfunction "PC14-OSC32_IN_F1") (pintype "bidirectional"))
      (node (ref "X1") (pin "1") (pinfunction "1_1") (pintype "passive"))
    )
    (net (code "165") (name "Net-(U5A-PC15-OSC32_OUT)") (class "Default")
      (node (ref "C11") (pin "2") (pinfunction "2_2") (pintype "passive"))
      (node (ref "U5") (pin "G1") (pinfunction "PC15-OSC32_OUT_G1") (pintype "bidirectional"))
      (node (ref "X1") (pin "2") (pinfunction "2_2") (pintype "passive"))
    )
    (net (code "166") (name "Net-(U5C-VBAT)") (class "Default")
      (node (ref "R93") (pin "1") (pinfunction "1_1") (pintype "passive"))
      (node (ref "U5") (pin "E2") (pinfunction "VBAT_E2") (pintype "power_in"))
    )
    (net (code "167") (name "Net-(U5C-VDD_USB)") (class "Default")
      (node (ref "C100") (pin "1") (pinfunction "1_1") (pintype "passive"))
      (node (ref "C95") (pin "1") (pinfunction "1_1") (pintype "passive"))
      (node (ref "JP4") (pin "2") (pintype "passive"))
      (node (ref "L1") (pin "1") (pinfunction "1_1") (pintype "passive"))
      (node (ref "U5") (pin "E12") (pinfunction "VDD_USB_E12") (pintype "power_in"))
    )
    (net (code "168") (name "VDD") (class "Default")
      (node (ref "R21") (pin "1") (pinfunction "1_1") (pintype "passive"))
      (node (ref "R42") (pin "1") (pinfunction "1_1") (pintype "passive"))
      (node (ref "R43") (pin "1") (pinfunction "1_1") (pintype "passive"))
    )
    (net (code "169") (name "VDDA") (class "Default")
      (node (ref "C7") (pin "1") (pinfunction "1_1") (pintype "passive"))
      (node (ref "C8") (pin "1") (pinfunction "1_1") (pintype "passive"))
      (node (ref "L1") (pin "2") (pinfunction "2_2") (pintype "passive"))
      (node (ref "R18") (pin "2") (pinfunction "2_2") (pintype "passive"))
      (node (ref "U5") (pin "L2") (pinfunction "VDDA_P_L2") (pintype "power_in"))
    )
    (net (code "170") (name "VDD_MCU") (class "Default")
      (node (ref "C12") (pin "1") (pinfunction "1_1") (pintype "passive"))
      (node (ref "C17") (pin "1") (pinfunction "1_1") (pintype "passive"))
      (node (ref "C18") (pin "1") (pinfunction "1_1") (pintype "passive"))
      (node (ref "C21") (pin "1") (pinfunction "1_1") (pintype "passive"))
      (node (ref "C22") (pin "1") (pinfunction "1_1") (pintype "passive"))
      (node (ref "C25") (pin "1") (pinfunction "1_1") (pintype "passive"))
      (node (ref "C26") (pin "1") (pinfunction "1_1") (pintype "passive"))
      (node (ref "C27") (pin "1") (pinfunction "1_1") (pintype "passive"))
      (node (ref "C28") (pin "1") (pinfunction "1_1") (pintype "passive"))
      (node (ref "C6") (pin "1") (pinfunction "1_1") (pintype "passive"))
      (node (ref "C81") (pin "1") (pinfunction "1_1") (pintype "passive"))
      (node (ref "C89") (pin "1") (pinfunction "1_1") (pintype "passive"))
      (node (ref "C97") (pin "1") (pinfunction "1_1") (pintype "passive"))
      (node (ref "C98") (pin "1") (pinfunction "1_1") (pintype "passive"))
      (node (ref "JP4") (pin "3") (pintype "passive"))
      (node (ref "R93") (pin "2") (pinfunction "2_2") (pintype "passive"))
      (node (ref "U5") (pin "A3") (pinfunction "VDD_3_A3") (pintype "power_in"))
      (node (ref "U5") (pin "A8") (pinfunction "VDD_6_A8") (pintype "power_in"))
      (node (ref "U5") (pin "B6") (pinfunction "VDDIO_2_B6") (pintype "power_in"))
      (node (ref "U5") (pin "C1") (pinfunction "VDD_13_C1") (pintype "power_in"))
      (node (ref "U5") (pin "C13") (pinfunction "VDD_2_C13") (pintype "power_in"))
      (node (ref "U5") (pin "F12") (pinfunction "VDDIO_1_F12") (pintype "power_in"))
      (node (ref "U5") (pin "G13") (pinfunction "VDD_4_G13") (pintype "power_in"))
      (node (ref "U5") (pin "G2") (pinfunction "VDD_5_G2") (pintype "power_in"))
      (node (ref "U5") (pin "H13") (pinfunction "VDD_8_H13") (pintype "power_in"))
      (node (ref "U5") (pin "L12") (pinfunction "VDD_1_L12") (pintype "power_in"))
      (node (ref "U5") (pin "N11") (pinfunction "VDD_11_N11") (pintype "power_in"))
      (node (ref "U5") (pin "N3") (pinfunction "VDD_10_N3") (pintype "power_in"))
      (node (ref "U5") (pin "N7") (pinfunction "VDD_7_N7") (pintype "power_in"))
    )
    (net (code "171") (name "VREF+") (class "Default")
      (node (ref "C13") (pin "1") (pinfunction "1_1") (pintype "passive"))
      (node (ref "C14") (pin "1") (pinfunction "1_1") (pintype "passive"))
      (node (ref "R18") (pin "1") (pinfunction "1_1") (pintype "passive"))
      (node (ref "U5") (pin "L1") (pinfunction "VREFP_L1") (pintype "power_in"))
    )
  )
)
